# nrf-beacon.net
KiCad netlist of a schematic drawn in EAGLE
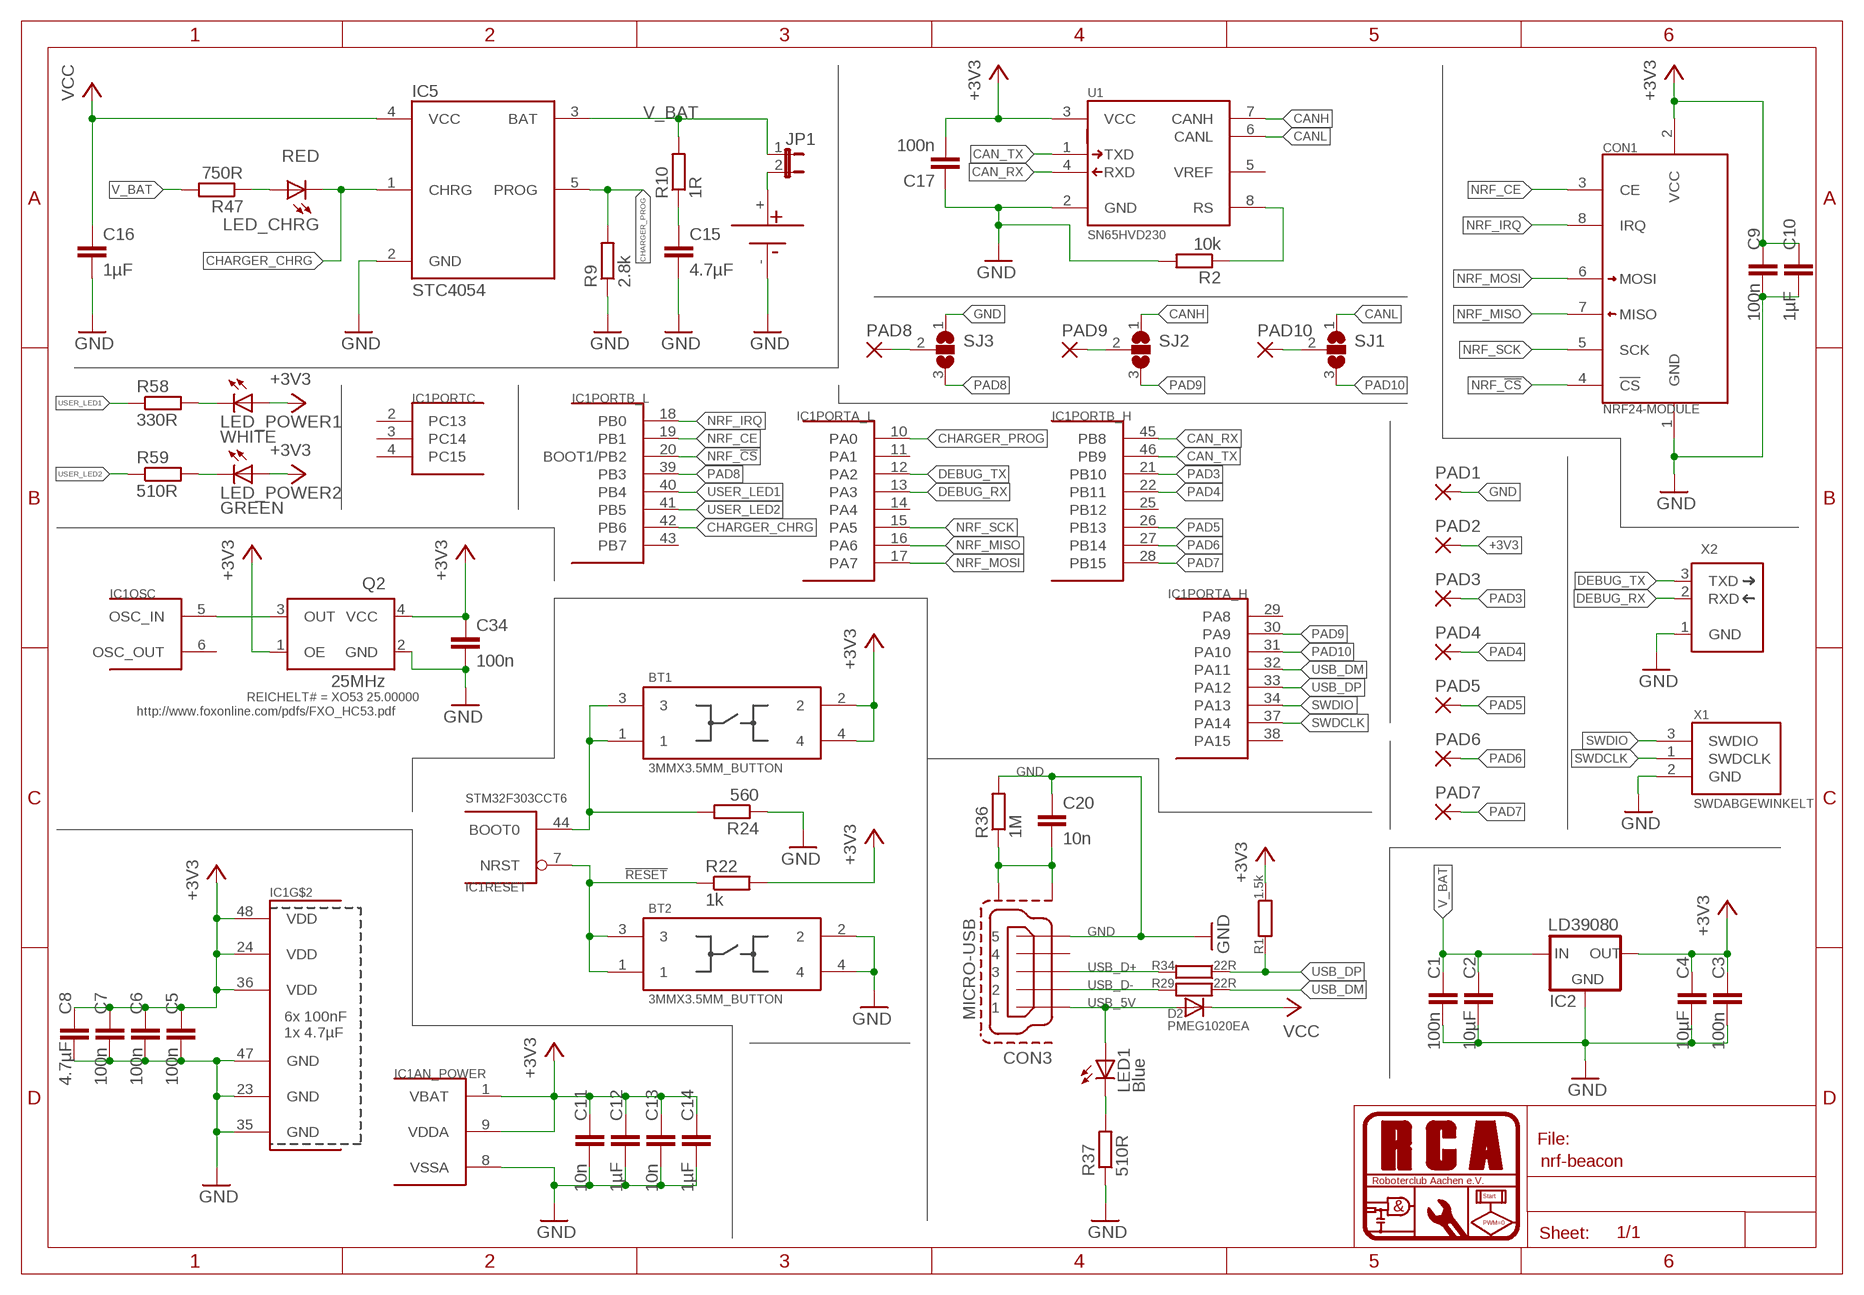
[diagram p0: schematic, sheet 1]

(export (version "E")
  (design (tool "Eeschema 10.0.6"))
  (components
    (comp (ref "BT1")
      (value "3MMX3.5MM_BUTTON")
      (footprint "eagle-import:3MMX3.5MM_BUTTON")
      (libsource (lib "eagle-import") (part "3MMX3.5MM_BUTTON"))
    )
    (comp (ref "BT2")
      (value "3MMX3.5MM_BUTTON")
      (footprint "eagle-import:3MMX3.5MM_BUTTON")
      (libsource (lib "eagle-import") (part "3MMX3.5MM_BUTTON"))
    )
    (comp (ref "C1")
      (value "100n")
      (footprint "eagle-import:C1206")
      (libsource (lib "eagle-import") (part "C-EUC1206"))
    )
    (comp (ref "C2")
      (value "10µF")
      (footprint "eagle-import:C1206")
      (libsource (lib "eagle-import") (part "C-EUC1206"))
    )
    (comp (ref "C3")
      (value "100n")
      (footprint "eagle-import:C1206")
      (libsource (lib "eagle-import") (part "C-EUC1206"))
    )
    (comp (ref "C4")
      (value "10µF")
      (footprint "eagle-import:C1206")
      (libsource (lib "eagle-import") (part "C-EUC1206"))
    )
    (comp (ref "C5")
      (value "100n")
      (footprint "eagle-import:C0603")
      (libsource (lib "eagle-import") (part "C-EUC0603"))
    )
    (comp (ref "C6")
      (value "100n")
      (footprint "eagle-import:C0603")
      (libsource (lib "eagle-import") (part "C-EUC0603"))
    )
    (comp (ref "C7")
      (value "100n")
      (footprint "eagle-import:C0603")
      (libsource (lib "eagle-import") (part "C-EUC0603"))
    )
    (comp (ref "C8")
      (value "4.7µF")
      (footprint "eagle-import:C0603")
      (libsource (lib "eagle-import") (part "C-EUC0603"))
    )
    (comp (ref "C9")
      (value "100n")
      (footprint "eagle-import:C0603")
      (libsource (lib "eagle-import") (part "resistor_C-EUC0603"))
    )
    (comp (ref "C10")
      (value "1µF")
      (footprint "eagle-import:C0603")
      (libsource (lib "eagle-import") (part "resistor_C-EUC0603"))
    )
    (comp (ref "C11")
      (value "10n")
      (footprint "eagle-import:C0603")
      (libsource (lib "eagle-import") (part "C-EUC0603"))
    )
    (comp (ref "C12")
      (value "1µF")
      (footprint "eagle-import:C0603")
      (libsource (lib "eagle-import") (part "C-EUC0603"))
    )
    (comp (ref "C13")
      (value "10n")
      (footprint "eagle-import:C0603")
      (libsource (lib "eagle-import") (part "C-EUC0603"))
    )
    (comp (ref "C14")
      (value "1µF")
      (footprint "eagle-import:C0603")
      (libsource (lib "eagle-import") (part "C-EUC0603"))
    )
    (comp (ref "C15")
      (value "4.7µF")
      (footprint "eagle-import:C0603")
      (libsource (lib "eagle-import") (part "C-EUC0603"))
    )
    (comp (ref "C16")
      (value "1µF")
      (footprint "eagle-import:C0603")
      (libsource (lib "eagle-import") (part "C-EUC0603"))
    )
    (comp (ref "C17")
      (value "100n")
      (footprint "eagle-import:C1206")
      (libsource (lib "eagle-import") (part "resistor_C-EUC1206"))
    )
    (comp (ref "C20")
      (value "10n")
      (footprint "eagle-import:C0805")
      (libsource (lib "eagle-import") (part "resistor_C-EUC0805"))
    )
    (comp (ref "C34")
      (value "100n")
      (footprint "eagle-import:C0603")
      (libsource (lib "eagle-import") (part "C-EUC0603"))
    )
    (comp (ref "CON1")
      (value "NRF24-MODULE")
      (footprint "eagle-import:NRF24-MODULE")
      (libsource (lib "eagle-import") (part "NRF24-MODULE"))
    )
    (comp (ref "CON3")
      (value "MICRO-USB")
      (footprint "eagle-import:MICRO-USB")
      (libsource (lib "eagle-import") (part "MICRO-USB"))
    )
    (comp (ref "D2")
      (value "PMEG1020EA")
      (footprint "eagle-import:SOD323-W")
      (fields (field (name "MANF") "NXP"))
      (libsource (lib "eagle-import") (part "DIODE-SOD323-W"))
    )
    (comp (ref "IC1")
      (value "STM32F303CCT6")
      (footprint "eagle-import:TQFP48")
      (libsource (lib "eagle-import") (part "STM32F303CCT6"))
    )
    (comp (ref "IC2")
      (value "LD39080")
      (footprint "eagle-import:DPAK")
      (libsource (lib "eagle-import") (part "LD39080"))
    )
    (comp (ref "IC5")
      (value "STC4054")
      (footprint "eagle-import:SOT23-5L")
      (libsource (lib "eagle-import") (part "STC4054"))
    )
    (comp (ref "JP1")
      (value "JP1E")
      (footprint "eagle-import:JP1")
      (libsource (lib "eagle-import") (part "JP1E"))
    )
    (comp (ref "LED1")
      (value "Blue")
      (footprint "eagle-import:CHIPLED_0805")
      (libsource (lib "eagle-import") (part "LEDCHIPLED_0805"))
    )
    (comp (ref "LED_CHRG")
      (value "RED")
      (footprint "eagle-import:CHIPLED_0805")
      (fields (field (name "REICHELT#") "SMD-LED 0805 RT"))
      (libsource (lib "eagle-import") (part "LEDCHIPLED_0805"))
    )
    (comp (ref "LED_POWER1")
      (value "WHITE")
      (footprint "eagle-import:CHIPLED_0805")
      (fields (field (name "REICHELT#") "SMD-LED 0805 GN"))
      (libsource (lib "eagle-import") (part "LEDCHIPLED_0805"))
    )
    (comp (ref "LED_POWER2")
      (value "GREEN")
      (footprint "eagle-import:CHIPLED_0805")
      (fields (field (name "REICHELT#") "SMD-LED 0805 GN"))
      (libsource (lib "eagle-import") (part "LEDCHIPLED_0805"))
    )
    (comp (ref "PAD1")
      (value "WIREPADSMD5-1,8")
      (footprint "eagle-import:5-1,8")
      (libsource (lib "eagle-import") (part "WIREPADSMD5-1,8"))
    )
    (comp (ref "PAD2")
      (value "WIREPADSMD5-1,8")
      (footprint "eagle-import:5-1,8")
      (libsource (lib "eagle-import") (part "WIREPADSMD5-1,8"))
    )
    (comp (ref "PAD3")
      (value "WIREPADSMD5-1,8")
      (footprint "eagle-import:5-1,8")
      (libsource (lib "eagle-import") (part "WIREPADSMD5-1,8"))
    )
    (comp (ref "PAD4")
      (value "WIREPADSMD5-1,8")
      (footprint "eagle-import:5-1,8")
      (libsource (lib "eagle-import") (part "WIREPADSMD5-1,8"))
    )
    (comp (ref "PAD5")
      (value "WIREPADSMD5-1,8")
      (footprint "eagle-import:5-1,8")
      (libsource (lib "eagle-import") (part "WIREPADSMD5-1,8"))
    )
    (comp (ref "PAD6")
      (value "WIREPADSMD5-1,8")
      (footprint "eagle-import:5-1,8")
      (libsource (lib "eagle-import") (part "WIREPADSMD5-1,8"))
    )
    (comp (ref "PAD7")
      (value "WIREPADSMD5-1,8")
      (footprint "eagle-import:5-1,8")
      (libsource (lib "eagle-import") (part "WIREPADSMD5-1,8"))
    )
    (comp (ref "PAD8")
      (value "WIREPADSMD5-1,8")
      (footprint "eagle-import:5-1,8")
      (libsource (lib "eagle-import") (part "WIREPADSMD5-1,8"))
    )
    (comp (ref "PAD9")
      (value "WIREPADSMD5-1,8")
      (footprint "eagle-import:5-1,8")
      (libsource (lib "eagle-import") (part "WIREPADSMD5-1,8"))
    )
    (comp (ref "PAD10")
      (value "WIREPADSMD5-1,8")
      (footprint "eagle-import:5-1,8")
      (libsource (lib "eagle-import") (part "WIREPADSMD5-1,8"))
    )
    (comp (ref "Q2")
      (value "25MHz")
      (footprint "eagle-import:XO53")
      (fields (field (name "REICHELT#") "XO53 25.00000"))
      (libsource (lib "eagle-import") (part "XO53"))
    )
    (comp (ref "R1")
      (value "1.5k")
      (footprint "eagle-import:M0805")
      (libsource (lib "eagle-import") (part "resistor_R-EU_M0805"))
    )
    (comp (ref "R2")
      (value "10k")
      (footprint "eagle-import:R0805")
      (libsource (lib "eagle-import") (part "R-EU_R0805"))
    )
    (comp (ref "R9")
      (value "2.8k")
      (footprint "eagle-import:R0603")
      (libsource (lib "eagle-import") (part "R-EU_R0603"))
    )
    (comp (ref "R10")
      (value "1R")
      (footprint "eagle-import:R0805")
      (libsource (lib "eagle-import") (part "R-EU_R0805"))
    )
    (comp (ref "R22")
      (value "1k")
      (footprint "eagle-import:R0603")
      (libsource (lib "eagle-import") (part "R-EU_R0603"))
    )
    (comp (ref "R24")
      (value "560")
      (footprint "eagle-import:R0805")
      (libsource (lib "eagle-import") (part "R-EU_R0805"))
    )
    (comp (ref "R29")
      (value "22R")
      (footprint "eagle-import:M0805")
      (libsource (lib "eagle-import") (part "resistor_R-EU_M0805"))
    )
    (comp (ref "R34")
      (value "22R")
      (footprint "eagle-import:M0805")
      (libsource (lib "eagle-import") (part "resistor_R-EU_M0805"))
    )
    (comp (ref "R36")
      (value "1M")
      (footprint "eagle-import:M0805")
      (libsource (lib "eagle-import") (part "resistor_R-EU_M0805"))
    )
    (comp (ref "R37")
      (value "510R")
      (footprint "eagle-import:M0805")
      (libsource (lib "eagle-import") (part "resistor_R-EU_M0805"))
    )
    (comp (ref "R47")
      (value "750R")
      (footprint "eagle-import:R0603")
      (libsource (lib "eagle-import") (part "resistor_R-EU_R0603"))
    )
    (comp (ref "R58")
      (value "330R")
      (footprint "eagle-import:R0603")
      (fields (field (name "DIGIKEY#") "311-560GRCT-ND"))
      (libsource (lib "eagle-import") (part "R-EU_R0603"))
    )
    (comp (ref "R59")
      (value "510R")
      (footprint "eagle-import:R0603")
      (fields (field (name "DIGIKEY#") "311-560GRCT-ND"))
      (libsource (lib "eagle-import") (part "R-EU_R0603"))
    )
    (comp (ref "SJ1")
      (value "SJ2W")
      (footprint "eagle-import:SJ_2")
      (libsource (lib "eagle-import") (part "SJ2W"))
    )
    (comp (ref "SJ2")
      (value "SJ2W")
      (footprint "eagle-import:SJ_2")
      (libsource (lib "eagle-import") (part "SJ2W"))
    )
    (comp (ref "SJ3")
      (value "SJ2W")
      (footprint "eagle-import:SJ_2")
      (libsource (lib "eagle-import") (part "SJ2W"))
    )
    (comp (ref "U$1")
      (value "BAT")
      (footprint "eagle-import:BAT")
      (libsource (lib "eagle-import") (part "BAT"))
    )
    (comp (ref "U1")
      (value "SN65HVD230")
      (footprint "eagle-import:SOIC-8")
      (libsource (lib "eagle-import") (part "SN65HVD230"))
    )
    (comp (ref "X1")
      (value "SWDABGEWINKELT")
      (footprint "eagle-import:7395-03")
      (libsource (lib "eagle-import") (part "SWDABGEWINKELT"))
    )
    (comp (ref "X2")
      (value "SERIAL_DEBUG_3PINL")
      (footprint "eagle-import:7395-03")
      (libsource (lib "eagle-import") (part "SERIAL_DEBUG_3PINL"))
    )
  )
  (nets
    (net (code "1") (name "+3V3") (class "Default")
      (node (ref "BT1") (pin "2") (pinfunction "2_2") (pintype "bidirectional"))
      (node (ref "BT1") (pin "4") (pinfunction "4_4") (pintype "bidirectional"))
      (node (ref "C10") (pin "1") (pinfunction "1_1") (pintype "passive"))
      (node (ref "C11") (pin "1") (pinfunction "1_1") (pintype "passive"))
      (node (ref "C12") (pin "1") (pinfunction "1_1") (pintype "passive"))
      (node (ref "C13") (pin "1") (pinfunction "1_1") (pintype "passive"))
      (node (ref "C14") (pin "1") (pinfunction "1_1") (pintype "passive"))
      (node (ref "C17") (pin "2") (pinfunction "2_2") (pintype "passive"))
      (node (ref "C3") (pin "1") (pinfunction "1_1") (pintype "passive"))
      (node (ref "C34") (pin "1") (pinfunction "1_1") (pintype "passive"))
      (node (ref "C4") (pin "1") (pinfunction "1_1") (pintype "passive"))
      (node (ref "C5") (pin "1") (pinfunction "1_1") (pintype "passive"))
      (node (ref "C6") (pin "1") (pinfunction "1_1") (pintype "passive"))
      (node (ref "C7") (pin "1") (pinfunction "1_1") (pintype "passive"))
      (node (ref "C8") (pin "1") (pinfunction "1_1") (pintype "passive"))
      (node (ref "C9") (pin "1") (pinfunction "1_1") (pintype "passive"))
      (node (ref "CON1") (pin "2") (pinfunction "VCC_2") (pintype "power_in"))
      (node (ref "IC1") (pin "1") (pinfunction "VBAT_1") (pintype "power_in"))
      (node (ref "IC1") (pin "24") (pinfunction "VDD_24") (pintype "power_in"))
      (node (ref "IC1") (pin "36") (pinfunction "VDD_36") (pintype "power_in"))
      (node (ref "IC1") (pin "48") (pinfunction "VDD_48") (pintype "power_in"))
      (node (ref "IC1") (pin "9") (pinfunction "VDDA_9") (pintype "power_in"))
      (node (ref "IC2") (pin "3") (pinfunction "OUT_3") (pintype "passive"))
      (node (ref "LED_POWER1") (pin "A") (pinfunction "A_A") (pintype "passive"))
      (node (ref "LED_POWER2") (pin "A") (pinfunction "A_A") (pintype "passive"))
      (node (ref "PAD2") (pin "1") (pinfunction "P_1") (pintype "passive"))
      (node (ref "Q2") (pin "1") (pinfunction "OE_1") (pintype "bidirectional"))
      (node (ref "Q2") (pin "4") (pinfunction "VCC_4") (pintype "bidirectional"))
      (node (ref "R1") (pin "1") (pinfunction "1_1") (pintype "passive"))
      (node (ref "R22") (pin "2") (pinfunction "2_2") (pintype "passive"))
      (node (ref "U1") (pin "3") (pinfunction "VCC_3") (pintype "power_in"))
    )
    (net (code "2") (name "/NRF_~{CS}") (class "Default")
      (node (ref "CON1") (pin "4") (pinfunction "~{CS}_4") (pintype "bidirectional"))
      (node (ref "IC1") (pin "20") (pinfunction "BOOT1/PB2_20") (pintype "bidirectional"))
    )
    (net (code "3") (name "/USB_5V") (class "Default")
      (node (ref "CON3") (pin "1") (pinfunction "1_1") (pintype "input"))
      (node (ref "D2") (pin "A") (pinfunction "A_A") (pintype "passive"))
      (node (ref "LED1") (pin "A") (pinfunction "A_A") (pintype "passive"))
    )
    (net (code "4") (name "/USB_D+") (class "Default")
      (node (ref "CON3") (pin "3") (pinfunction "3_3") (pintype "input"))
      (node (ref "R34") (pin "2") (pinfunction "2_2") (pintype "passive"))
    )
    (net (code "5") (name "/USB_D-") (class "Default")
      (node (ref "CON3") (pin "2") (pinfunction "2_2") (pintype "input"))
      (node (ref "R29") (pin "2") (pinfunction "2_2") (pintype "passive"))
    )
    (net (code "6") (name "/VREF") (class "Default")
      (node (ref "U1") (pin "5") (pinfunction "VREF_5") (pintype "power_in"))
    )
    (net (code "7") (name "/~{RESET}") (class "Default")
      (node (ref "BT2") (pin "1") (pinfunction "1_1") (pintype "bidirectional"))
      (node (ref "BT2") (pin "3") (pinfunction "3_3") (pintype "bidirectional"))
      (node (ref "IC1") (pin "7") (pinfunction "NRST_7") (pintype "input"))
      (node (ref "R22") (pin "1") (pinfunction "1_1") (pintype "passive"))
    )
    (net (code "8") (name "CANH") (class "Default")
      (node (ref "SJ2") (pin "1") (pinfunction "1_1") (pintype "passive"))
      (node (ref "U1") (pin "7") (pinfunction "CANH_7") (pintype "bidirectional"))
    )
    (net (code "9") (name "CANL") (class "Default")
      (node (ref "SJ1") (pin "1") (pinfunction "1_1") (pintype "passive"))
      (node (ref "U1") (pin "6") (pinfunction "CANL_6") (pintype "bidirectional"))
    )
    (net (code "10") (name "CAN_RX") (class "Default")
      (node (ref "IC1") (pin "45") (pinfunction "PB8_45") (pintype "bidirectional"))
      (node (ref "U1") (pin "4") (pinfunction "RXD_4") (pintype "output"))
    )
    (net (code "11") (name "CAN_TX") (class "Default")
      (node (ref "IC1") (pin "46") (pinfunction "PB9_46") (pintype "bidirectional"))
      (node (ref "U1") (pin "1") (pinfunction "TXD_1") (pintype "input"))
    )
    (net (code "12") (name "CHARGER_CHRG") (class "Default")
      (node (ref "IC1") (pin "42") (pinfunction "PB6_42") (pintype "bidirectional"))
      (node (ref "IC5") (pin "1") (pinfunction "CHRG_1") (pintype "bidirectional"))
      (node (ref "LED_CHRG") (pin "C") (pinfunction "C_C") (pintype "passive"))
    )
    (net (code "13") (name "CHARGER_PROG") (class "Default")
      (node (ref "IC1") (pin "10") (pinfunction "PA0_10") (pintype "bidirectional"))
      (node (ref "IC5") (pin "5") (pinfunction "PROG_5") (pintype "bidirectional"))
      (node (ref "R9") (pin "2") (pinfunction "2_2") (pintype "passive"))
    )
    (net (code "14") (name "DEBUG_RX") (class "Default")
      (node (ref "IC1") (pin "13") (pinfunction "PA3_13") (pintype "bidirectional"))
      (node (ref "X2") (pin "2") (pinfunction "RXD_2") (pintype "bidirectional"))
    )
    (net (code "15") (name "DEBUG_TX") (class "Default")
      (node (ref "IC1") (pin "12") (pinfunction "PA2_12") (pintype "bidirectional"))
      (node (ref "X2") (pin "3") (pinfunction "TXD_3") (pintype "bidirectional"))
    )
    (net (code "16") (name "GND") (class "Default")
      (node (ref "BT2") (pin "2") (pinfunction "2_2") (pintype "bidirectional"))
      (node (ref "BT2") (pin "4") (pinfunction "4_4") (pintype "bidirectional"))
      (node (ref "C1") (pin "2") (pinfunction "2_2") (pintype "passive"))
      (node (ref "C10") (pin "2") (pinfunction "2_2") (pintype "passive"))
      (node (ref "C11") (pin "2") (pinfunction "2_2") (pintype "passive"))
      (node (ref "C12") (pin "2") (pinfunction "2_2") (pintype "passive"))
      (node (ref "C13") (pin "2") (pinfunction "2_2") (pintype "passive"))
      (node (ref "C14") (pin "2") (pinfunction "2_2") (pintype "passive"))
      (node (ref "C15") (pin "2") (pinfunction "2_2") (pintype "passive"))
      (node (ref "C16") (pin "2") (pinfunction "2_2") (pintype "passive"))
      (node (ref "C17") (pin "1") (pinfunction "1_1") (pintype "passive"))
      (node (ref "C2") (pin "2") (pinfunction "2_2") (pintype "passive"))
      (node (ref "C20") (pin "1") (pinfunction "1_1") (pintype "passive"))
      (node (ref "C3") (pin "2") (pinfunction "2_2") (pintype "passive"))
      (node (ref "C34") (pin "2") (pinfunction "2_2") (pintype "passive"))
      (node (ref "C4") (pin "2") (pinfunction "2_2") (pintype "passive"))
      (node (ref "C5") (pin "2") (pinfunction "2_2") (pintype "passive"))
      (node (ref "C6") (pin "2") (pinfunction "2_2") (pintype "passive"))
      (node (ref "C7") (pin "2") (pinfunction "2_2") (pintype "passive"))
      (node (ref "C8") (pin "2") (pinfunction "2_2") (pintype "passive"))
      (node (ref "C9") (pin "2") (pinfunction "2_2") (pintype "passive"))
      (node (ref "CON1") (pin "1") (pinfunction "GND_1") (pintype "power_in"))
      (node (ref "CON3") (pin "5") (pinfunction "5_5") (pintype "input"))
      (node (ref "IC1") (pin "23") (pinfunction "GND_23") (pintype "power_in"))
      (node (ref "IC1") (pin "35") (pinfunction "GND_35") (pintype "power_in"))
      (node (ref "IC1") (pin "47") (pinfunction "GND_47") (pintype "power_in"))
      (node (ref "IC1") (pin "8") (pinfunction "VSSA_8") (pintype "power_in"))
      (node (ref "IC2") (pin "2") (pinfunction "GND_2") (pintype "input"))
      (node (ref "IC5") (pin "2") (pinfunction "GND_2") (pintype "bidirectional"))
      (node (ref "PAD1") (pin "1") (pinfunction "P_1") (pintype "passive"))
      (node (ref "Q2") (pin "2") (pinfunction "GND_2") (pintype "bidirectional"))
      (node (ref "R2") (pin "2") (pinfunction "2_2") (pintype "passive"))
      (node (ref "R24") (pin "1") (pinfunction "1_1") (pintype "passive"))
      (node (ref "R36") (pin "2") (pinfunction "2_2") (pintype "passive"))
      (node (ref "R37") (pin "1") (pinfunction "1_1") (pintype "passive"))
      (node (ref "R9") (pin "1") (pinfunction "1_1") (pintype "passive"))
      (node (ref "SJ3") (pin "1") (pinfunction "1_1") (pintype "passive"))
      (node (ref "U$1") (pin "-") (pinfunction "-_-") (pintype "power_in"))
      (node (ref "U1") (pin "2") (pinfunction "GND_2") (pintype "power_in"))
      (node (ref "X1") (pin "2") (pinfunction "GND_2") (pintype "bidirectional"))
      (node (ref "X2") (pin "1") (pinfunction "GND_1") (pintype "power_in"))
    )
    (net (code "17") (name "NRF_CE") (class "Default")
      (node (ref "CON1") (pin "3") (pinfunction "CE_3") (pintype "bidirectional"))
      (node (ref "IC1") (pin "19") (pinfunction "PB1_19") (pintype "bidirectional"))
    )
    (net (code "18") (name "NRF_IRQ") (class "Default")
      (node (ref "CON1") (pin "8") (pinfunction "IRQ_8") (pintype "bidirectional"))
      (node (ref "IC1") (pin "18") (pinfunction "PB0_18") (pintype "bidirectional"))
    )
    (net (code "19") (name "NRF_MISO") (class "Default")
      (node (ref "CON1") (pin "7") (pinfunction "MISO_7") (pintype "bidirectional"))
      (node (ref "IC1") (pin "16") (pinfunction "PA6_16") (pintype "bidirectional"))
    )
    (net (code "20") (name "NRF_MOSI") (class "Default")
      (node (ref "CON1") (pin "6") (pinfunction "MOSI_6") (pintype "bidirectional"))
      (node (ref "IC1") (pin "17") (pinfunction "PA7_17") (pintype "bidirectional"))
    )
    (net (code "21") (name "NRF_SCK") (class "Default")
      (node (ref "CON1") (pin "5") (pinfunction "SCK_5") (pintype "bidirectional"))
      (node (ref "IC1") (pin "15") (pinfunction "PA5_15") (pintype "bidirectional"))
    )
    (net (code "22") (name "Net-(C15-Pad1)") (class "Default")
      (node (ref "C15") (pin "1") (pinfunction "1_1") (pintype "passive"))
      (node (ref "R10") (pin "1") (pinfunction "1_1") (pintype "passive"))
    )
    (net (code "23") (name "Net-(C20-Pad2)") (class "Default")
      (node (ref "C20") (pin "2") (pinfunction "2_2") (pintype "passive"))
      (node (ref "CON3") (pin "SHIELDING1") (pinfunction "SHIELDING1_SHIELDING1") (pintype "passive"))
      (node (ref "CON3") (pin "SHIELDING2") (pinfunction "SHIELDING2_SHIELDING2") (pintype "passive"))
      (node (ref "R36") (pin "1") (pinfunction "1_1") (pintype "passive"))
    )
    (net (code "24") (name "Net-(IC1C-OSC_IN)") (class "Default")
      (node (ref "IC1") (pin "5") (pinfunction "OSC_IN_5") (pintype "input"))
      (node (ref "Q2") (pin "3") (pinfunction "OUT_3") (pintype "bidirectional"))
    )
    (net (code "25") (name "Net-(IC1I-BOOT0)") (class "Default")
      (node (ref "BT1") (pin "1") (pinfunction "1_1") (pintype "bidirectional"))
      (node (ref "BT1") (pin "3") (pinfunction "3_3") (pintype "bidirectional"))
      (node (ref "IC1") (pin "44") (pinfunction "BOOT0_44") (pintype "input"))
      (node (ref "R24") (pin "2") (pinfunction "2_2") (pintype "passive"))
    )
    (net (code "26") (name "Net-(JP1-Pad2)") (class "Default")
      (node (ref "JP1") (pin "2") (pinfunction "2_2") (pintype "passive"))
      (node (ref "U$1") (pin "+") (pinfunction "+_+") (pintype "power_in"))
    )
    (net (code "27") (name "Net-(LED1-PadC)") (class "Default")
      (node (ref "LED1") (pin "C") (pinfunction "C_C") (pintype "passive"))
      (node (ref "R37") (pin "2") (pinfunction "2_2") (pintype "passive"))
    )
    (net (code "28") (name "Net-(LED_CHRG-PadA)") (class "Default")
      (node (ref "LED_CHRG") (pin "A") (pinfunction "A_A") (pintype "passive"))
      (node (ref "R47") (pin "1") (pinfunction "1_1") (pintype "passive"))
    )
    (net (code "29") (name "Net-(LED_POWER1-PadC)") (class "Default")
      (node (ref "LED_POWER1") (pin "C") (pinfunction "C_C") (pintype "passive"))
      (node (ref "R58") (pin "2") (pinfunction "2_2") (pintype "passive"))
    )
    (net (code "30") (name "Net-(LED_POWER2-PadC)") (class "Default")
      (node (ref "LED_POWER2") (pin "C") (pinfunction "C_C") (pintype "passive"))
      (node (ref "R59") (pin "2") (pinfunction "2_2") (pintype "passive"))
    )
    (net (code "31") (name "Net-(PAD8-P)") (class "Default")
      (node (ref "PAD8") (pin "1") (pinfunction "P_1") (pintype "passive"))
      (node (ref "SJ3") (pin "2") (pinfunction "2_2") (pintype "passive"))
    )
    (net (code "32") (name "Net-(PAD9-P)") (class "Default")
      (node (ref "PAD9") (pin "1") (pinfunction "P_1") (pintype "passive"))
      (node (ref "SJ2") (pin "2") (pinfunction "2_2") (pintype "passive"))
    )
    (net (code "33") (name "Net-(PAD10-P)") (class "Default")
      (node (ref "PAD10") (pin "1") (pinfunction "P_1") (pintype "passive"))
      (node (ref "SJ1") (pin "2") (pinfunction "2_2") (pintype "passive"))
    )
    (net (code "34") (name "Net-(U1-RS)") (class "Default")
      (node (ref "R2") (pin "1") (pinfunction "1_1") (pintype "passive"))
      (node (ref "U1") (pin "8") (pinfunction "RS_8") (pintype "bidirectional"))
    )
    (net (code "35") (name "PAD3") (class "Default")
      (node (ref "IC1") (pin "21") (pinfunction "PB10_21") (pintype "bidirectional"))
      (node (ref "PAD3") (pin "1") (pinfunction "P_1") (pintype "passive"))
    )
    (net (code "36") (name "PAD4") (class "Default")
      (node (ref "IC1") (pin "22") (pinfunction "PB11_22") (pintype "bidirectional"))
      (node (ref "PAD4") (pin "1") (pinfunction "P_1") (pintype "passive"))
    )
    (net (code "37") (name "PAD5") (class "Default")
      (node (ref "IC1") (pin "26") (pinfunction "PB13_26") (pintype "bidirectional"))
      (node (ref "PAD5") (pin "1") (pinfunction "P_1") (pintype "passive"))
    )
    (net (code "38") (name "PAD6") (class "Default")
      (node (ref "IC1") (pin "27") (pinfunction "PB14_27") (pintype "bidirectional"))
      (node (ref "PAD6") (pin "1") (pinfunction "P_1") (pintype "passive"))
    )
    (net (code "39") (name "PAD7") (class "Default")
      (node (ref "IC1") (pin "28") (pinfunction "PB15_28") (pintype "bidirectional"))
      (node (ref "PAD7") (pin "1") (pinfunction "P_1") (pintype "passive"))
    )
    (net (code "40") (name "PAD8") (class "Default")
      (node (ref "IC1") (pin "39") (pinfunction "PB3_39") (pintype "bidirectional"))
      (node (ref "SJ3") (pin "3") (pinfunction "3_3") (pintype "passive"))
    )
    (net (code "41") (name "PAD9") (class "Default")
      (node (ref "IC1") (pin "30") (pinfunction "PA9_30") (pintype "bidirectional"))
      (node (ref "SJ2") (pin "3") (pinfunction "3_3") (pintype "passive"))
    )
    (net (code "42") (name "PAD10") (class "Default")
      (node (ref "IC1") (pin "31") (pinfunction "PA10_31") (pintype "bidirectional"))
      (node (ref "SJ1") (pin "3") (pinfunction "3_3") (pintype "passive"))
    )
    (net (code "43") (name "SWDCLK") (class "Default")
      (node (ref "IC1") (pin "37") (pinfunction "PA14_37") (pintype "bidirectional"))
      (node (ref "X1") (pin "1") (pinfunction "SWDCLK_1") (pintype "bidirectional"))
    )
    (net (code "44") (name "SWDIO") (class "Default")
      (node (ref "IC1") (pin "34") (pinfunction "PA13_34") (pintype "bidirectional"))
      (node (ref "X1") (pin "3") (pinfunction "SWDIO_3") (pintype "bidirectional"))
    )
    (net (code "45") (name "USB_DM") (class "Default")
      (node (ref "IC1") (pin "32") (pinfunction "PA11_32") (pintype "bidirectional"))
      (node (ref "R29") (pin "1") (pinfunction "1_1") (pintype "passive"))
    )
    (net (code "46") (name "USB_DP") (class "Default")
      (node (ref "IC1") (pin "33") (pinfunction "PA12_33") (pintype "bidirectional"))
      (node (ref "R1") (pin "2") (pinfunction "2_2") (pintype "passive"))
      (node (ref "R34") (pin "1") (pinfunction "1_1") (pintype "passive"))
    )
    (net (code "47") (name "USER_LED1") (class "Default")
      (node (ref "IC1") (pin "40") (pinfunction "PB4_40") (pintype "bidirectional"))
      (node (ref "R58") (pin "1") (pinfunction "1_1") (pintype "passive"))
    )
    (net (code "48") (name "USER_LED2") (class "Default")
      (node (ref "IC1") (pin "41") (pinfunction "PB5_41") (pintype "bidirectional"))
      (node (ref "R59") (pin "1") (pinfunction "1_1") (pintype "passive"))
    )
    (net (code "49") (name "VCC") (class "Default")
      (node (ref "C16") (pin "1") (pinfunction "1_1") (pintype "passive"))
      (node (ref "D2") (pin "C") (pinfunction "C_C") (pintype "passive"))
      (node (ref "IC5") (pin "4") (pinfunction "VCC_4") (pintype "power_in"))
    )
    (net (code "50") (name "V_BAT") (class "Default")
      (node (ref "C1") (pin "1") (pinfunction "1_1") (pintype "passive"))
      (node (ref "C2") (pin "1") (pinfunction "1_1") (pintype "passive"))
      (node (ref "IC2") (pin "1") (pinfunction "IN_1") (pintype "input"))
      (node (ref "IC5") (pin "3") (pinfunction "BAT_3") (pintype "power_in"))
      (node (ref "JP1") (pin "1") (pinfunction "1_1") (pintype "passive"))
      (node (ref "R10") (pin "2") (pinfunction "2_2") (pintype "passive"))
      (node (ref "R47") (pin "2") (pinfunction "2_2") (pintype "passive"))
    )
    (net (code "51") (name "unconnected-(CON3-Pad4)") (class "Default")
      (node (ref "CON3") (pin "4") (pinfunction "4_4") (pintype "input"))
    )
    (net (code "52") (name "unconnected-(IC1C-OSC_OUT-Pad6)") (class "Default")
      (node (ref "IC1") (pin "6") (pinfunction "OSC_OUT_6") (pintype "output"))
    )
    (net (code "53") (name "unconnected-(IC1D-PA8-Pad29)") (class "Default")
      (node (ref "IC1") (pin "29") (pinfunction "PA8_29") (pintype "bidirectional"))
    )
    (net (code "54") (name "unconnected-(IC1D-PA15-Pad38)") (class "Default")
      (node (ref "IC1") (pin "38") (pinfunction "PA15_38") (pintype "bidirectional"))
    )
    (net (code "55") (name "unconnected-(IC1E-PA1-Pad11)") (class "Default")
      (node (ref "IC1") (pin "11") (pinfunction "PA1_11") (pintype "bidirectional"))
    )
    (net (code "56") (name "unconnected-(IC1E-PA4-Pad14)") (class "Default")
      (node (ref "IC1") (pin "14") (pinfunction "PA4_14") (pintype "bidirectional"))
    )
    (net (code "57") (name "unconnected-(IC1F-PB12-Pad25)") (class "Default")
      (node (ref "IC1") (pin "25") (pinfunction "PB12_25") (pintype "bidirectional"))
    )
    (net (code "58") (name "unconnected-(IC1G-PB7-Pad43)") (class "Default")
      (node (ref "IC1") (pin "43") (pinfunction "PB7_43") (pintype "bidirectional"))
    )
    (net (code "59") (name "unconnected-(IC1H-PC13-Pad2)") (class "Default")
      (node (ref "IC1") (pin "2") (pinfunction "PC13_2") (pintype "bidirectional"))
    )
    (net (code "60") (name "unconnected-(IC1H-PC14-Pad3)") (class "Default")
      (node (ref "IC1") (pin "3") (pinfunction "PC14_3") (pintype "bidirectional"))
    )
    (net (code "61") (name "unconnected-(IC1H-PC15-Pad4)") (class "Default")
      (node (ref "IC1") (pin "4") (pinfunction "PC15_4") (pintype "bidirectional"))
    )
  )
)
